# v1_0.net
KiCad netlist of a schematic drawn in Altium Designer
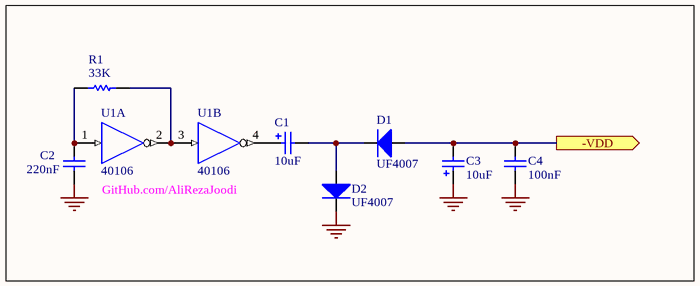
[diagram p0: v1.0.SchDoc]

(export (version "E")
  (design (tool "Eeschema 10.0.6"))
  (components
    (comp (ref "C1")
      (value "10uF")
      (footprint "CAPPR2.5-5x6")
      (description "Polarized Capacitor (Radial)")
      (fields (field (name "MANUFACTURER") "Generic Components") (field (name "PUBLISHER") "Altium Limited"))
      (libsource (lib "Miscellaneous Devices") (part "Cap Pol1"))
    )
    (comp (ref "C2")
      (value "220nF")
      (footprint "CAPNTO5.08-7.37x3.94")
      (description "Capacitor")
      (fields (field (name "PUBLISHER") "Altium Limited"))
      (libsource (lib "Miscellaneous Devices") (part "Cap"))
    )
    (comp (ref "C3")
      (value "10uF")
      (footprint "CAPPR2.5-5x6")
      (description "Polarized Capacitor (Radial)")
      (fields (field (name "MANUFACTURER") "Generic Components") (field (name "PUBLISHER") "Altium Limited"))
      (libsource (lib "Miscellaneous Devices") (part "Cap Pol1"))
    )
    (comp (ref "C4")
      (value "100nF")
      (footprint "CAPNTO2.54-3.05x1.78A")
      (description "Capacitor")
      (fields (field (name "MANUFACTURER") "Generic Components") (field (name "PUBLISHER") "Altium Limited"))
      (libsource (lib "Miscellaneous Devices") (part "Cap"))
    )
    (comp (ref "D1")
      (value "UF4007")
      (footprint "DIODE0.5_")
      (description "Default Diode")
      (fields (field (name "MANUFACTURER") "Generic Components") (field (name "PUBLISHER") "Altium Limited"))
      (libsource (lib "Miscellaneous Devices") (part "Diode"))
    )
    (comp (ref "D2")
      (value "UF4007")
      (footprint "DIODE0.5_")
      (description "Default Diode")
      (fields (field (name "MANUFACTURER") "Generic Components") (field (name "PUBLISHER") "Altium Limited"))
      (libsource (lib "Miscellaneous Devices") (part "Diode"))
    )
    (comp (ref "R1")
      (value "33K")
      (footprint "AXIAL-0.4")
      (description "Resistor")
      (fields (field (name "PUBLISHER") "Altium Limited"))
      (libsource (lib "Miscellaneous Devices") (part "Res1"))
    )
    (comp (ref "U1")
      (value "40106")
      (footprint "DIP14")
      (description "Hex inverting Schmitt trigger, 14-Pin")
      (fields (field (name "PUBLISHER") "Altium Limited"))
      (libsource (lib "my Libraries") (part "40106"))
    )
  )
  (nets
    (net (code "1") (name "/-VDD") (class "Default")
      (node (ref "C3") (pin "2") (pinfunction "2_2") (pintype "passive"))
      (node (ref "C4") (pin "2") (pinfunction "2_2") (pintype "passive"))
      (node (ref "D1") (pin "1") (pinfunction "A_1") (pintype "passive"))
    )
    (net (code "2") (name "GND") (class "Default")
      (node (ref "C2") (pin "1") (pinfunction "1_1") (pintype "passive"))
      (node (ref "C3") (pin "1") (pinfunction "1_1") (pintype "passive"))
      (node (ref "C4") (pin "1") (pinfunction "1_1") (pintype "passive"))
      (node (ref "D2") (pin "2") (pinfunction "K_2") (pintype "passive"))
    )
    (net (code "3") (name "Net-(D1-K)") (class "Default")
      (node (ref "C1") (pin "2") (pinfunction "2_2") (pintype "passive"))
      (node (ref "D1") (pin "2") (pinfunction "K_2") (pintype "passive"))
      (node (ref "D2") (pin "1") (pinfunction "A_1") (pintype "passive"))
    )
    (net (code "4") (name "Net-(U1A-I)") (class "Default")
      (node (ref "C2") (pin "2") (pinfunction "2_2") (pintype "passive"))
      (node (ref "R1") (pin "2") (pinfunction "2_2") (pintype "passive"))
      (node (ref "U1") (pin "1") (pinfunction "I_1") (pintype "input"))
    )
    (net (code "5") (name "Net-(U1A-~{O})") (class "Default")
      (node (ref "R1") (pin "1") (pinfunction "1_1") (pintype "passive"))
      (node (ref "U1") (pin "2") (pinfunction "~{O}_2") (pintype "output"))
      (node (ref "U1") (pin "3") (pinfunction "I_3") (pintype "input"))
    )
    (net (code "6") (name "Net-(U1B-~{O})") (class "Default")
      (node (ref "C1") (pin "1") (pinfunction "1_1") (pintype "passive"))
      (node (ref "U1") (pin "4") (pinfunction "~{O}_4") (pintype "output"))
    )
  )
)
